# SlippiBoardRev1.net
KiCad netlist of a schematic drawn in EAGLE
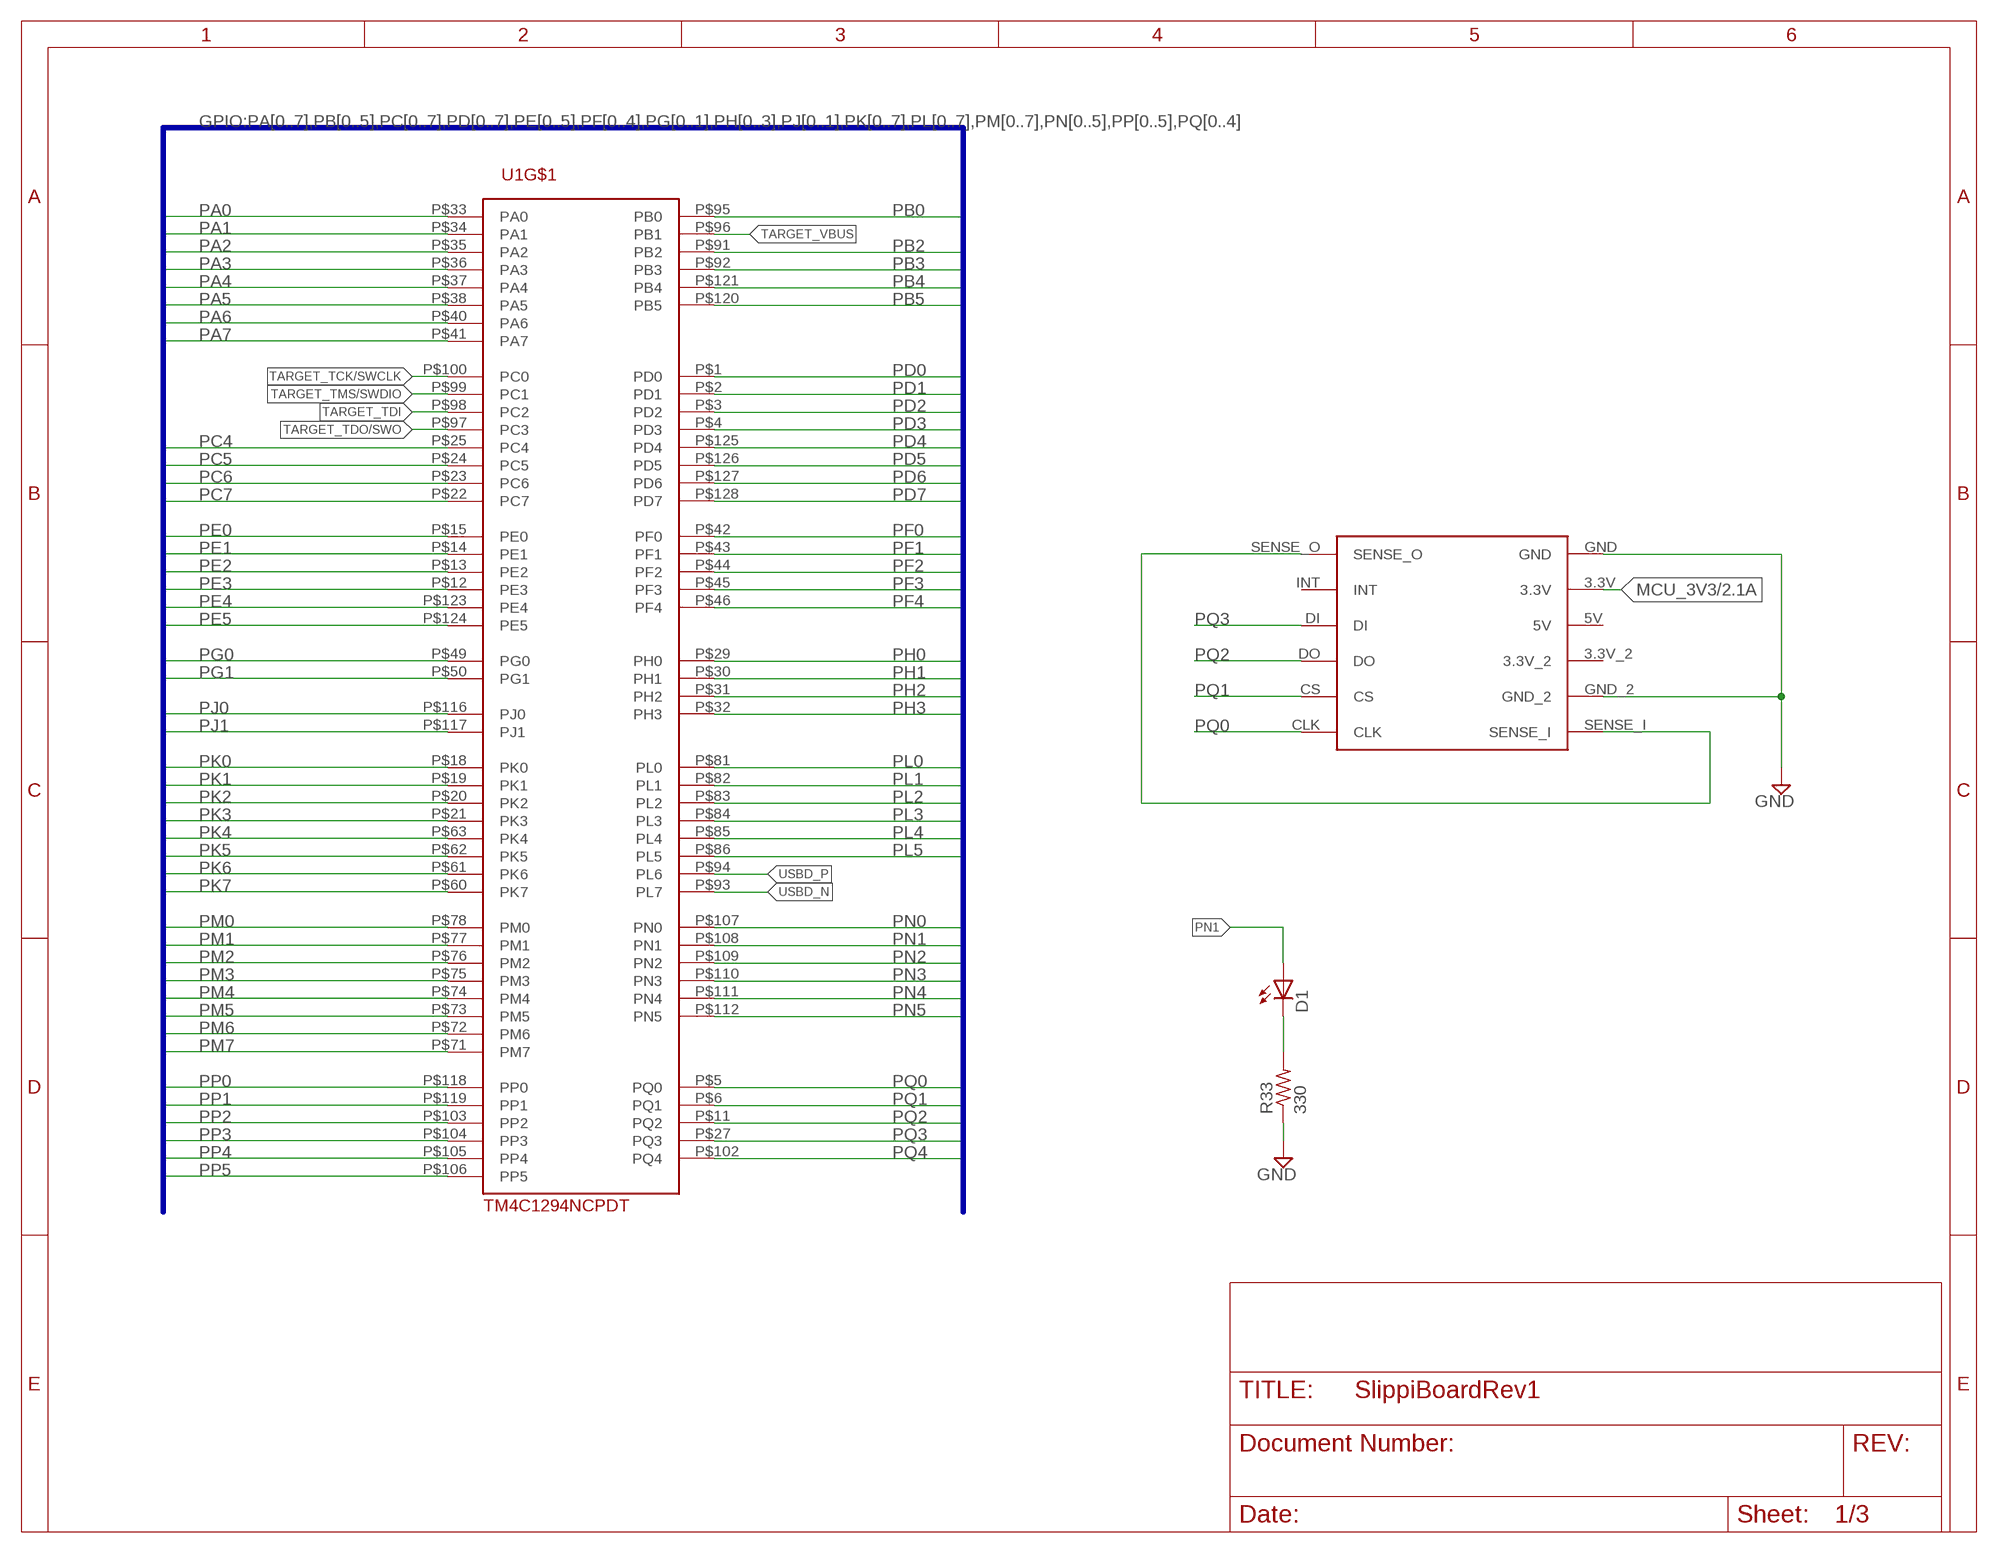
[diagram p0: schematic, sheet 1]
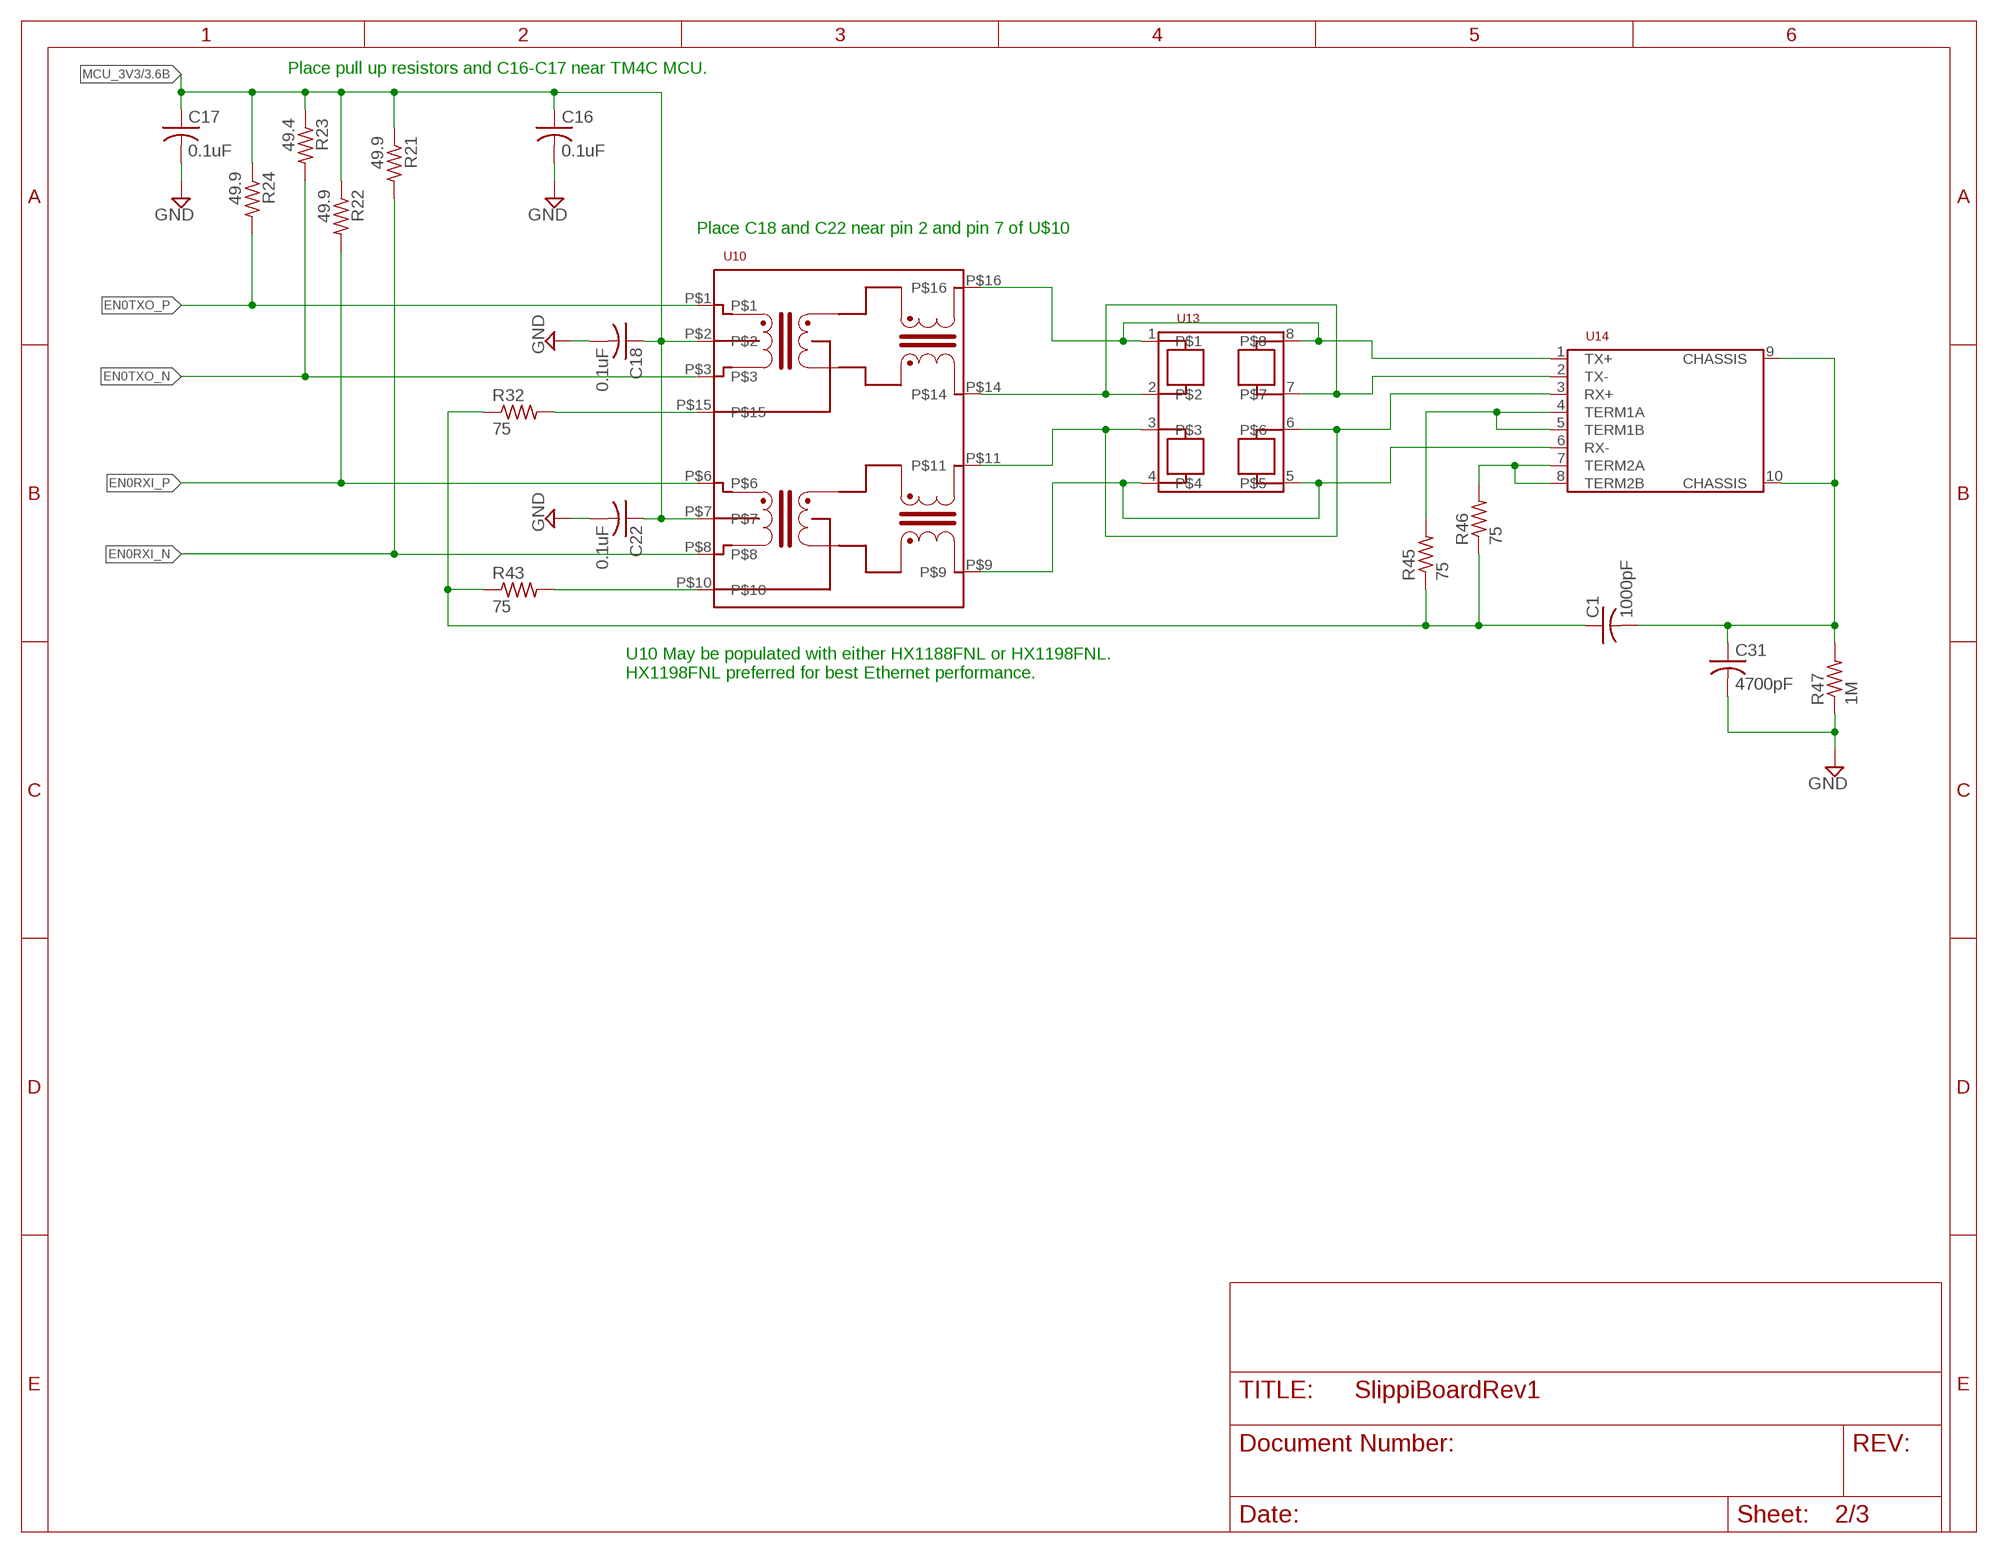
[diagram p1: schematic, sheet 2]
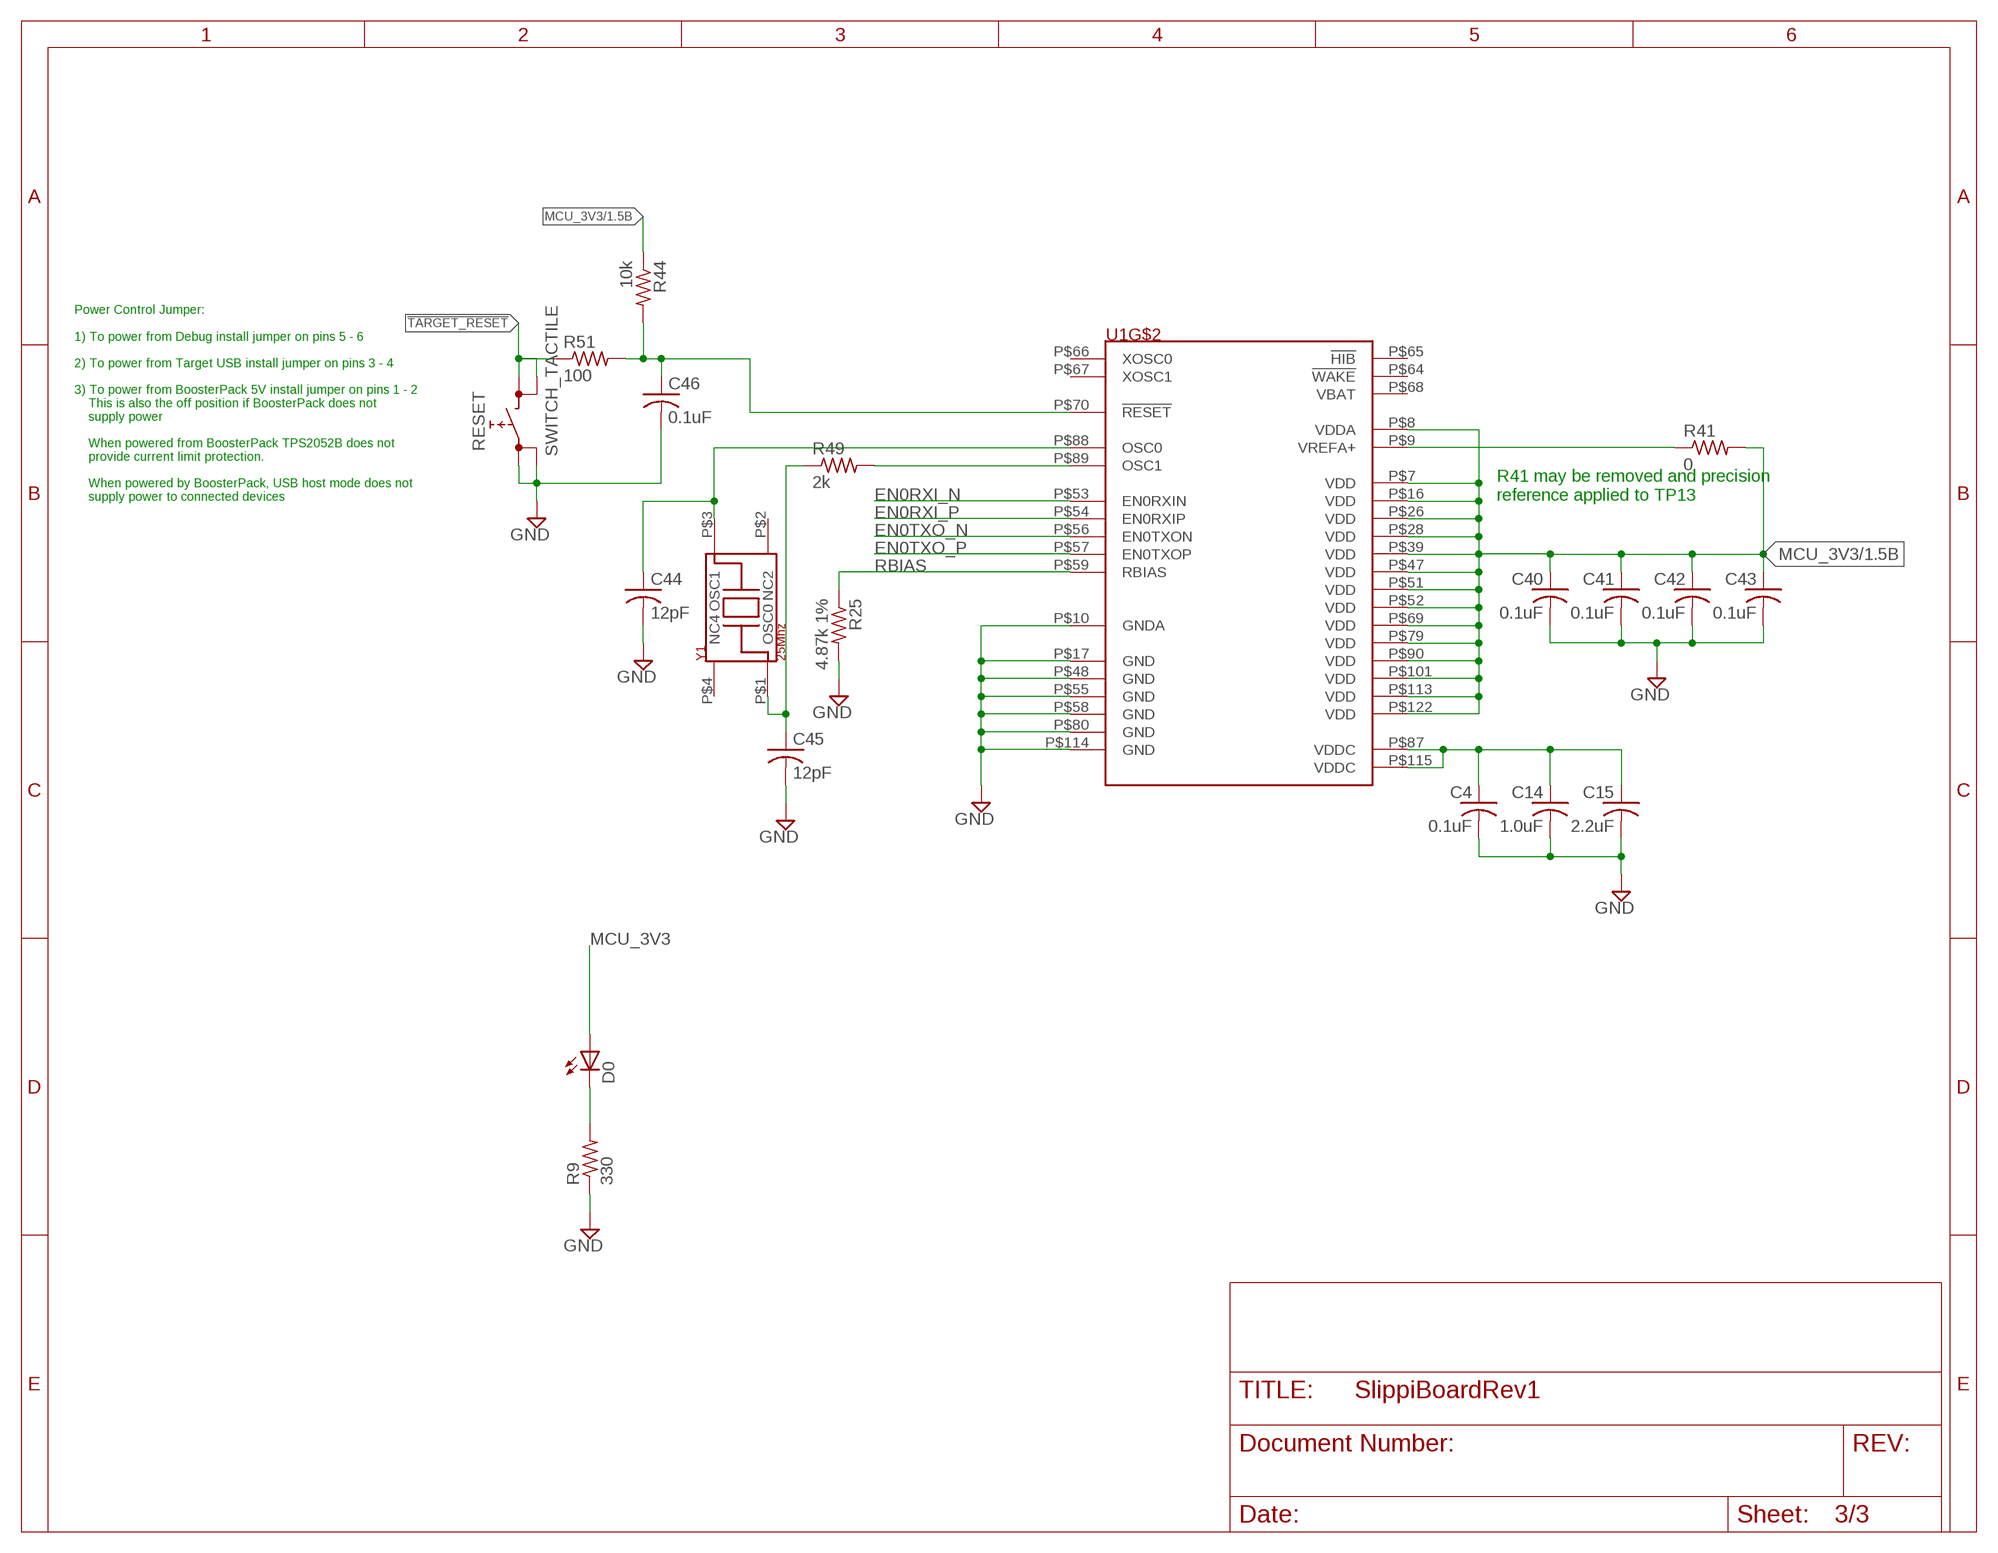
[diagram p2: schematic, sheet 3]

(export (version "E")
  (design (tool "Eeschema 10.0.6"))
  (components
    (comp (ref "D1")
      (value "LEDCHIPLED_0603")
      (footprint "eagle-import:CHIPLED_0603")
      (libsource (lib "eagle-import") (part "LEDCHIPLED_0603"))
    )
    (comp (ref "R33")
      (value "330")
      (footprint "eagle-import:R0402")
      (libsource (lib "eagle-import") (part "ek-tm4c129exl_R-US_R0402"))
    )
    (comp (ref "U$1")
      (value "GC_MEMCARD_CON")
      (footprint "eagle-import:GC_MEMCARD_CON")
      (libsource (lib "eagle-import") (part "GC_MEMCARD_CON"))
    )
    (comp (ref "U1")
      (value "TM4C1294NCPDT")
      (footprint "eagle-import:TQFP-128")
      (fields (field (name "GNUM") "G50-QF128-C1294-ALH"))
      (libsource (lib "eagle-import") (part "TM4C1294NCPDT"))
    )
    (comp (ref "C4")
      (value "0.1uF")
      (footprint "eagle-import:C0402")
      (libsource (lib "eagle-import") (part "ek-tm4c129exl_C-USC0402"))
    )
    (comp (ref "C14")
      (value "1.0uF")
      (footprint "eagle-import:C0402")
      (libsource (lib "eagle-import") (part "ek-tm4c129exl_C-USC0402"))
    )
    (comp (ref "C15")
      (value "2.2uF")
      (footprint "eagle-import:C0603K")
      (fields (field (name "DIGIKEY_PARTNUM") "311-1451-2-ND"))
      (libsource (lib "eagle-import") (part "ek-tm4c129exl_C-USC0603K"))
    )
    (comp (ref "C40")
      (value "0.1uF")
      (footprint "eagle-import:C0402")
      (libsource (lib "eagle-import") (part "ek-tm4c129exl_C-USC0402"))
    )
    (comp (ref "C41")
      (value "0.1uF")
      (footprint "eagle-import:C0402")
      (libsource (lib "eagle-import") (part "ek-tm4c129exl_C-USC0402"))
    )
    (comp (ref "C42")
      (value "0.1uF")
      (footprint "eagle-import:C0402")
      (libsource (lib "eagle-import") (part "ek-tm4c129exl_C-USC0402"))
    )
    (comp (ref "C43")
      (value "0.1uF")
      (footprint "eagle-import:C0402")
      (libsource (lib "eagle-import") (part "ek-tm4c129exl_C-USC0402"))
    )
    (comp (ref "C44")
      (value "12pF")
      (footprint "eagle-import:C0402")
      (libsource (lib "eagle-import") (part "ek-tm4c129exl_C-USC0402"))
    )
    (comp (ref "C45")
      (value "12pF")
      (footprint "eagle-import:C0402")
      (libsource (lib "eagle-import") (part "ek-tm4c129exl_C-USC0402"))
    )
    (comp (ref "C46")
      (value "0.1uF")
      (footprint "eagle-import:C0402")
      (libsource (lib "eagle-import") (part "ek-tm4c129exl_C-USC0402"))
    )
    (comp (ref "D0")
      (value "LEDCHIPLED_0603")
      (footprint "eagle-import:CHIPLED_0603")
      (libsource (lib "eagle-import") (part "LEDCHIPLED_0603"))
    )
    (comp (ref "R9")
      (value "330")
      (footprint "eagle-import:R0402")
      (libsource (lib "eagle-import") (part "ek-tm4c129exl_R-US_R0402"))
    )
    (comp (ref "R25")
      (value "4.87k 1%")
      (footprint "eagle-import:R0402")
      (libsource (lib "eagle-import") (part "ek-tm4c129exl_R-US_R0402"))
    )
    (comp (ref "R41")
      (value "0")
      (footprint "eagle-import:R0402")
      (libsource (lib "eagle-import") (part "ek-tm4c129exl_R-US_R0402"))
    )
    (comp (ref "R44")
      (value "10k")
      (footprint "eagle-import:R0402")
      (libsource (lib "eagle-import") (part "ek-tm4c129exl_R-US_R0402"))
    )
    (comp (ref "R49")
      (value "2k")
      (footprint "eagle-import:R0402")
      (libsource (lib "eagle-import") (part "ek-tm4c129exl_R-US_R0402"))
    )
    (comp (ref "R51")
      (value "100")
      (footprint "eagle-import:R0402")
      (libsource (lib "eagle-import") (part "ek-tm4c129exl_R-US_R0402"))
    )
    (comp (ref "RESET")
      (value "SWITCH_TACTILE")
      (footprint "eagle-import:SWITCH_6MM_6MM_TE_CON_SMD")
      (libsource (lib "eagle-import") (part "SWITCH_TACTILE"))
    )
    (comp (ref "Y1")
      (value "25Mhz")
      (footprint "eagle-import:NDK3.2X2.5")
      (libsource (lib "eagle-import") (part "NX3225GA"))
    )
    (comp (ref "C1")
      (value "1000pF")
      (footprint "eagle-import:C1210")
      (libsource (lib "eagle-import") (part "C-USC1210"))
    )
    (comp (ref "C16")
      (value "0.1uF")
      (footprint "eagle-import:C0402")
      (libsource (lib "eagle-import") (part "ek-tm4c129exl_C-USC0402"))
    )
    (comp (ref "C17")
      (value "0.1uF")
      (footprint "eagle-import:C0402")
      (libsource (lib "eagle-import") (part "ek-tm4c129exl_C-USC0402"))
    )
    (comp (ref "C18")
      (value "0.1uF")
      (footprint "eagle-import:C0402")
      (libsource (lib "eagle-import") (part "ek-tm4c129exl_C-USC0402"))
    )
    (comp (ref "C22")
      (value "0.1uF")
      (footprint "eagle-import:C0402")
      (libsource (lib "eagle-import") (part "ek-tm4c129exl_C-USC0402"))
    )
    (comp (ref "C31")
      (value "4700pF")
      (footprint "eagle-import:C1812")
      (libsource (lib "eagle-import") (part "ek-tm4c129exl_C-USC1812"))
    )
    (comp (ref "R21")
      (value "49.9")
      (footprint "eagle-import:R0402")
      (libsource (lib "eagle-import") (part "ek-tm4c129exl_R-US_R0402"))
    )
    (comp (ref "R22")
      (value "49.9")
      (footprint "eagle-import:R0402")
      (libsource (lib "eagle-import") (part "ek-tm4c129exl_R-US_R0402"))
    )
    (comp (ref "R23")
      (value "49.4")
      (footprint "eagle-import:R0402")
      (libsource (lib "eagle-import") (part "ek-tm4c129exl_R-US_R0402"))
    )
    (comp (ref "R24")
      (value "49.9")
      (footprint "eagle-import:R0402")
      (libsource (lib "eagle-import") (part "ek-tm4c129exl_R-US_R0402"))
    )
    (comp (ref "R32")
      (value "75")
      (footprint "eagle-import:R0402")
      (libsource (lib "eagle-import") (part "ek-tm4c129exl_R-US_R0402"))
    )
    (comp (ref "R43")
      (value "75")
      (footprint "eagle-import:R0402")
      (libsource (lib "eagle-import") (part "ek-tm4c129exl_R-US_R0402"))
    )
    (comp (ref "R45")
      (value "75")
      (footprint "eagle-import:R0402")
      (libsource (lib "eagle-import") (part "ek-tm4c129exl_R-US_R0402"))
    )
    (comp (ref "R46")
      (value "75")
      (footprint "eagle-import:R0402")
      (libsource (lib "eagle-import") (part "ek-tm4c129exl_R-US_R0402"))
    )
    (comp (ref "R47")
      (value "1M")
      (footprint "eagle-import:R1206")
      (libsource (lib "eagle-import") (part "R-US_R1206"))
    )
    (comp (ref "U10")
      (value "MAG_PULSE_HX1188FNL")
      (footprint "eagle-import:MAG_PULSE_HX1188FNL")
      (libsource (lib "eagle-import") (part "MAG_PULSE_HX1188FNL"))
    )
    (comp (ref "U13")
      (value "SLVU2.8-4")
      (footprint "eagle-import:D8")
      (libsource (lib "eagle-import") (part "SLVU2.8-4"))
    )
    (comp (ref "U14")
      (value "JACK_RJ45_NOMAG_NOLED_TECON")
      (footprint "eagle-import:RJ45_TE_CON_NOMAG_NOLED")
      (libsource (lib "eagle-import") (part "JACK_RJ45_NOMAG_NOLED_TECON"))
    )
  )
  (nets
    (net (code "2") (name "EN0RXI_N") (class "Default")
      (node (ref "R21") (pin "2") (pinfunction "2_2") (pintype "passive"))
      (node (ref "U1") (pin "P$53") (pinfunction "EN0RXIN_P$53") (pintype "bidirectional"))
      (node (ref "U10") (pin "P$8") (pinfunction "P$8_P$8") (pintype "bidirectional"))
    )
    (net (code "3") (name "EN0RXI_P") (class "Default")
      (node (ref "R22") (pin "2") (pinfunction "2_2") (pintype "passive"))
      (node (ref "U1") (pin "P$54") (pinfunction "EN0RXIP_P$54") (pintype "bidirectional"))
      (node (ref "U10") (pin "P$6") (pinfunction "P$6_P$6") (pintype "bidirectional"))
    )
    (net (code "4") (name "EN0TXO_N") (class "Default")
      (node (ref "R23") (pin "2") (pinfunction "2_2") (pintype "passive"))
      (node (ref "U1") (pin "P$56") (pinfunction "EN0TXON_P$56") (pintype "bidirectional"))
      (node (ref "U10") (pin "P$3") (pinfunction "P$3_P$3") (pintype "bidirectional"))
    )
    (net (code "5") (name "EN0TXO_P") (class "Default")
      (node (ref "R24") (pin "2") (pinfunction "2_2") (pintype "passive"))
      (node (ref "U1") (pin "P$57") (pinfunction "EN0TXOP_P$57") (pintype "bidirectional"))
      (node (ref "U10") (pin "P$1") (pinfunction "P$1_P$1") (pintype "bidirectional"))
    )
    (net (code "6") (name "GND") (class "Default")
      (node (ref "C14") (pin "2") (pinfunction "2_2") (pintype "passive"))
      (node (ref "C15") (pin "2") (pinfunction "2_2") (pintype "passive"))
      (node (ref "C16") (pin "2") (pinfunction "2_2") (pintype "passive"))
      (node (ref "C17") (pin "2") (pinfunction "2_2") (pintype "passive"))
      (node (ref "C18") (pin "2") (pinfunction "2_2") (pintype "passive"))
      (node (ref "C22") (pin "2") (pinfunction "2_2") (pintype "passive"))
      (node (ref "C31") (pin "2") (pinfunction "2_2") (pintype "passive"))
      (node (ref "C4") (pin "2") (pinfunction "2_2") (pintype "passive"))
      (node (ref "C40") (pin "2") (pinfunction "2_2") (pintype "passive"))
      (node (ref "C41") (pin "2") (pinfunction "2_2") (pintype "passive"))
      (node (ref "C42") (pin "2") (pinfunction "2_2") (pintype "passive"))
      (node (ref "C43") (pin "2") (pinfunction "2_2") (pintype "passive"))
      (node (ref "C44") (pin "2") (pinfunction "2_2") (pintype "passive"))
      (node (ref "C45") (pin "2") (pinfunction "2_2") (pintype "passive"))
      (node (ref "C46") (pin "2") (pinfunction "2_2") (pintype "passive"))
      (node (ref "R25") (pin "2") (pinfunction "2_2") (pintype "passive"))
      (node (ref "R33") (pin "1") (pinfunction "1_1") (pintype "passive"))
      (node (ref "R47") (pin "1") (pinfunction "1_1") (pintype "passive"))
      (node (ref "R9") (pin "1") (pinfunction "1_1") (pintype "passive"))
      (node (ref "RESET") (pin "P$1") (pinfunction "0_P$1") (pintype "passive"))
      (node (ref "RESET") (pin "P$2") (pinfunction "0_P$2") (pintype "passive"))
      (node (ref "U$1") (pin "GND") (pinfunction "GND_GND") (pintype "bidirectional"))
      (node (ref "U$1") (pin "GND_2") (pinfunction "GND_2_GND_2") (pintype "bidirectional"))
      (node (ref "U1") (pin "P$10") (pinfunction "GNDA_P$10") (pintype "bidirectional"))
      (node (ref "U1") (pin "P$114") (pinfunction "GND_P$114") (pintype "bidirectional"))
      (node (ref "U1") (pin "P$17") (pinfunction "GND_P$17") (pintype "bidirectional"))
      (node (ref "U1") (pin "P$48") (pinfunction "GND_P$48") (pintype "bidirectional"))
      (node (ref "U1") (pin "P$55") (pinfunction "GND_P$55") (pintype "bidirectional"))
      (node (ref "U1") (pin "P$58") (pinfunction "GND_P$58") (pintype "bidirectional"))
      (node (ref "U1") (pin "P$80") (pinfunction "GND_P$80") (pintype "bidirectional"))
    )
    (net (code "7") (name "MCU_3V3") (class "Default")
      (node (ref "C16") (pin "1") (pinfunction "1_1") (pintype "passive"))
      (node (ref "C17") (pin "1") (pinfunction "1_1") (pintype "passive"))
      (node (ref "C18") (pin "1") (pinfunction "1_1") (pintype "passive"))
      (node (ref "C22") (pin "1") (pinfunction "1_1") (pintype "passive"))
      (node (ref "C40") (pin "1") (pinfunction "1_1") (pintype "passive"))
      (node (ref "C41") (pin "1") (pinfunction "1_1") (pintype "passive"))
      (node (ref "C42") (pin "1") (pinfunction "1_1") (pintype "passive"))
      (node (ref "C43") (pin "1") (pinfunction "1_1") (pintype "passive"))
      (node (ref "D0") (pin "A") (pinfunction "A_A") (pintype "passive"))
      (node (ref "R21") (pin "1") (pinfunction "1_1") (pintype "passive"))
      (node (ref "R22") (pin "1") (pinfunction "1_1") (pintype "passive"))
      (node (ref "R23") (pin "1") (pinfunction "1_1") (pintype "passive"))
      (node (ref "R24") (pin "1") (pinfunction "1_1") (pintype "passive"))
      (node (ref "R41") (pin "2") (pinfunction "2_2") (pintype "passive"))
      (node (ref "R44") (pin "1") (pinfunction "1_1") (pintype "passive"))
      (node (ref "U$1") (pin "3.3V") (pinfunction "3.3V_3.3V") (pintype "bidirectional"))
      (node (ref "U1") (pin "P$101") (pinfunction "VDD_P$101") (pintype "bidirectional"))
      (node (ref "U1") (pin "P$113") (pinfunction "VDD_P$113") (pintype "bidirectional"))
      (node (ref "U1") (pin "P$122") (pinfunction "VDD_P$122") (pintype "bidirectional"))
      (node (ref "U1") (pin "P$16") (pinfunction "VDD_P$16") (pintype "bidirectional"))
      (node (ref "U1") (pin "P$26") (pinfunction "VDD_P$26") (pintype "bidirectional"))
      (node (ref "U1") (pin "P$28") (pinfunction "VDD_P$28") (pintype "bidirectional"))
      (node (ref "U1") (pin "P$39") (pinfunction "VDD_P$39") (pintype "bidirectional"))
      (node (ref "U1") (pin "P$47") (pinfunction "VDD_P$47") (pintype "bidirectional"))
      (node (ref "U1") (pin "P$51") (pinfunction "VDD_P$51") (pintype "bidirectional"))
      (node (ref "U1") (pin "P$52") (pinfunction "VDD_P$52") (pintype "bidirectional"))
      (node (ref "U1") (pin "P$69") (pinfunction "VDD_P$69") (pintype "bidirectional"))
      (node (ref "U1") (pin "P$7") (pinfunction "VDD_P$7") (pintype "bidirectional"))
      (node (ref "U1") (pin "P$79") (pinfunction "VDD_P$79") (pintype "bidirectional"))
      (node (ref "U1") (pin "P$8") (pinfunction "VDDA_P$8") (pintype "bidirectional"))
      (node (ref "U1") (pin "P$90") (pinfunction "VDD_P$90") (pintype "bidirectional"))
      (node (ref "U10") (pin "P$2") (pinfunction "P$2_P$2") (pintype "bidirectional"))
      (node (ref "U10") (pin "P$7") (pinfunction "P$7_P$7") (pintype "bidirectional"))
    )
    (net (code "8") (name "Net-(C1-Pad1)") (class "Default")
      (node (ref "C1") (pin "1") (pinfunction "1_1") (pintype "passive"))
      (node (ref "R32") (pin "1") (pinfunction "1_1") (pintype "passive"))
      (node (ref "R43") (pin "1") (pinfunction "1_1") (pintype "passive"))
      (node (ref "R45") (pin "1") (pinfunction "1_1") (pintype "passive"))
      (node (ref "R46") (pin "1") (pinfunction "1_1") (pintype "passive"))
    )
    (net (code "9") (name "Net-(C1-Pad2)") (class "Default")
      (node (ref "C1") (pin "2") (pinfunction "2_2") (pintype "passive"))
      (node (ref "C31") (pin "1") (pinfunction "1_1") (pintype "passive"))
      (node (ref "R47") (pin "2") (pinfunction "2_2") (pintype "passive"))
      (node (ref "U14") (pin "10") (pinfunction "CHASSIS_10") (pintype "bidirectional"))
      (node (ref "U14") (pin "9") (pinfunction "CHASSIS_9") (pintype "bidirectional"))
    )
    (net (code "10") (name "Net-(C14-Pad1)") (class "Default")
      (node (ref "C14") (pin "1") (pinfunction "1_1") (pintype "passive"))
      (node (ref "C15") (pin "1") (pinfunction "1_1") (pintype "passive"))
      (node (ref "C4") (pin "1") (pinfunction "1_1") (pintype "passive"))
      (node (ref "U1") (pin "P$115") (pinfunction "VDDC_P$115") (pintype "bidirectional"))
      (node (ref "U1") (pin "P$87") (pinfunction "VDDC_P$87") (pintype "bidirectional"))
    )
    (net (code "11") (name "Net-(D0-PadC)") (class "Default")
      (node (ref "D0") (pin "C") (pinfunction "C_C") (pintype "passive"))
      (node (ref "R9") (pin "2") (pinfunction "2_2") (pintype "passive"))
    )
    (net (code "12") (name "Net-(D1-PadC)") (class "Default")
      (node (ref "D1") (pin "C") (pinfunction "C_C") (pintype "passive"))
      (node (ref "R33") (pin "2") (pinfunction "2_2") (pintype "passive"))
    )
    (net (code "13") (name "Net-(R32-Pad2)") (class "Default")
      (node (ref "R32") (pin "2") (pinfunction "2_2") (pintype "passive"))
      (node (ref "U10") (pin "P$15") (pinfunction "P$15_P$15") (pintype "bidirectional"))
    )
    (net (code "14") (name "Net-(R43-Pad2)") (class "Default")
      (node (ref "R43") (pin "2") (pinfunction "2_2") (pintype "passive"))
      (node (ref "U10") (pin "P$10") (pinfunction "P$10_P$10") (pintype "bidirectional"))
    )
    (net (code "15") (name "Net-(U$1-PadSENSE_I)") (class "Default")
      (node (ref "U$1") (pin "SENSE_I") (pinfunction "SENSE_I_SENSE_I") (pintype "bidirectional"))
      (node (ref "U$1") (pin "SENSE_O") (pinfunction "SENSE_O_SENSE_O") (pintype "bidirectional"))
    )
    (net (code "16") (name "Net-(U1B-OSC0)") (class "Default")
      (node (ref "C44") (pin "1") (pinfunction "1_1") (pintype "passive"))
      (node (ref "U1") (pin "P$88") (pinfunction "OSC0_P$88") (pintype "bidirectional"))
      (node (ref "Y1") (pin "P$3") (pinfunction "OSC1_P$3") (pintype "bidirectional"))
    )
    (net (code "17") (name "Net-(U1B-OSC1)") (class "Default")
      (node (ref "R49") (pin "2") (pinfunction "2_2") (pintype "passive"))
      (node (ref "U1") (pin "P$89") (pinfunction "OSC1_P$89") (pintype "bidirectional"))
    )
    (net (code "18") (name "Net-(U1B-VREFA+)") (class "Default")
      (node (ref "R41") (pin "1") (pinfunction "1_1") (pintype "passive"))
      (node (ref "U1") (pin "P$9") (pinfunction "VREFA+_P$9") (pintype "bidirectional"))
    )
    (net (code "19") (name "Net-(U1B-~{RESET})") (class "Default")
      (node (ref "C46") (pin "1") (pinfunction "1_1") (pintype "passive"))
      (node (ref "R44") (pin "2") (pinfunction "2_2") (pintype "passive"))
      (node (ref "R51") (pin "2") (pinfunction "2_2") (pintype "passive"))
      (node (ref "U1") (pin "P$70") (pinfunction "~{RESET}_P$70") (pintype "bidirectional"))
    )
    (net (code "20") (name "Net-(U13-P$1)") (class "Default")
      (node (ref "U10") (pin "P$16") (pinfunction "P$16_P$16") (pintype "bidirectional"))
      (node (ref "U13") (pin "1") (pinfunction "P$1_1") (pintype "bidirectional"))
      (node (ref "U13") (pin "8") (pinfunction "P$8_8") (pintype "bidirectional"))
      (node (ref "U14") (pin "1") (pinfunction "TX+_1") (pintype "bidirectional"))
    )
    (net (code "21") (name "Net-(U13-P$2)") (class "Default")
      (node (ref "U10") (pin "P$14") (pinfunction "P$14_P$14") (pintype "bidirectional"))
      (node (ref "U13") (pin "2") (pinfunction "P$2_2") (pintype "bidirectional"))
      (node (ref "U13") (pin "7") (pinfunction "P$7_7") (pintype "bidirectional"))
      (node (ref "U14") (pin "2") (pinfunction "TX-_2") (pintype "bidirectional"))
    )
    (net (code "22") (name "Net-(U13-P$3)") (class "Default")
      (node (ref "U10") (pin "P$11") (pinfunction "P$11_P$11") (pintype "bidirectional"))
      (node (ref "U13") (pin "3") (pinfunction "P$3_3") (pintype "bidirectional"))
      (node (ref "U13") (pin "6") (pinfunction "P$6_6") (pintype "bidirectional"))
      (node (ref "U14") (pin "3") (pinfunction "RX+_3") (pintype "bidirectional"))
    )
    (net (code "23") (name "Net-(U13-P$4)") (class "Default")
      (node (ref "U10") (pin "P$9") (pinfunction "P$9_P$9") (pintype "bidirectional"))
      (node (ref "U13") (pin "4") (pinfunction "P$4_4") (pintype "bidirectional"))
      (node (ref "U13") (pin "5") (pinfunction "P$5_5") (pintype "bidirectional"))
      (node (ref "U14") (pin "6") (pinfunction "RX-_6") (pintype "bidirectional"))
    )
    (net (code "24") (name "Net-(U14-TERM1A)") (class "Default")
      (node (ref "R45") (pin "2") (pinfunction "2_2") (pintype "passive"))
      (node (ref "U14") (pin "4") (pinfunction "TERM1A_4") (pintype "bidirectional"))
      (node (ref "U14") (pin "5") (pinfunction "TERM1B_5") (pintype "bidirectional"))
    )
    (net (code "25") (name "Net-(U14-TERM2A)") (class "Default")
      (node (ref "R46") (pin "2") (pinfunction "2_2") (pintype "passive"))
      (node (ref "U14") (pin "7") (pinfunction "TERM2A_7") (pintype "bidirectional"))
      (node (ref "U14") (pin "8") (pinfunction "TERM2B_8") (pintype "bidirectional"))
    )
    (net (code "26") (name "Net-(Y1-OSC0)") (class "Default")
      (node (ref "C45") (pin "1") (pinfunction "1_1") (pintype "passive"))
      (node (ref "R49") (pin "1") (pinfunction "1_1") (pintype "passive"))
      (node (ref "Y1") (pin "P$1") (pinfunction "OSC0_P$1") (pintype "bidirectional"))
    )
    (net (code "27") (name "PA0") (class "Default")
      (node (ref "U1") (pin "P$33") (pinfunction "PA0_P$33") (pintype "bidirectional"))
    )
    (net (code "28") (name "PA1") (class "Default")
      (node (ref "U1") (pin "P$34") (pinfunction "PA1_P$34") (pintype "bidirectional"))
    )
    (net (code "29") (name "PA2") (class "Default")
      (node (ref "U1") (pin "P$35") (pinfunction "PA2_P$35") (pintype "bidirectional"))
    )
    (net (code "30") (name "PA3") (class "Default")
      (node (ref "U1") (pin "P$36") (pinfunction "PA3_P$36") (pintype "bidirectional"))
    )
    (net (code "31") (name "PA4") (class "Default")
      (node (ref "U1") (pin "P$37") (pinfunction "PA4_P$37") (pintype "bidirectional"))
    )
    (net (code "32") (name "PA5") (class "Default")
      (node (ref "U1") (pin "P$38") (pinfunction "PA5_P$38") (pintype "bidirectional"))
    )
    (net (code "33") (name "PA6") (class "Default")
      (node (ref "U1") (pin "P$40") (pinfunction "PA6_P$40") (pintype "bidirectional"))
    )
    (net (code "34") (name "PA7") (class "Default")
      (node (ref "U1") (pin "P$41") (pinfunction "PA7_P$41") (pintype "bidirectional"))
    )
    (net (code "35") (name "PB0") (class "Default")
      (node (ref "U1") (pin "P$95") (pinfunction "PB0_P$95") (pintype "bidirectional"))
    )
    (net (code "36") (name "PB2") (class "Default")
      (node (ref "U1") (pin "P$91") (pinfunction "PB2_P$91") (pintype "bidirectional"))
    )
    (net (code "37") (name "PB3") (class "Default")
      (node (ref "U1") (pin "P$92") (pinfunction "PB3_P$92") (pintype "bidirectional"))
    )
    (net (code "38") (name "PB4") (class "Default")
      (node (ref "U1") (pin "P$121") (pinfunction "PB4_P$121") (pintype "bidirectional"))
    )
    (net (code "39") (name "PB5") (class "Default")
      (node (ref "U1") (pin "P$120") (pinfunction "PB5_P$120") (pintype "bidirectional"))
    )
    (net (code "40") (name "PC4") (class "Default")
      (node (ref "U1") (pin "P$25") (pinfunction "PC4_P$25") (pintype "bidirectional"))
    )
    (net (code "41") (name "PC5") (class "Default")
      (node (ref "U1") (pin "P$24") (pinfunction "PC5_P$24") (pintype "bidirectional"))
    )
    (net (code "42") (name "PC6") (class "Default")
      (node (ref "U1") (pin "P$23") (pinfunction "PC6_P$23") (pintype "bidirectional"))
    )
    (net (code "43") (name "PC7") (class "Default")
      (node (ref "U1") (pin "P$22") (pinfunction "PC7_P$22") (pintype "bidirectional"))
    )
    (net (code "44") (name "PD0") (class "Default")
      (node (ref "U1") (pin "P$1") (pinfunction "PD0_P$1") (pintype "bidirectional"))
    )
    (net (code "45") (name "PD1") (class "Default")
      (node (ref "U1") (pin "P$2") (pinfunction "PD1_P$2") (pintype "bidirectional"))
    )
    (net (code "46") (name "PD2") (class "Default")
      (node (ref "U1") (pin "P$3") (pinfunction "PD2_P$3") (pintype "bidirectional"))
    )
    (net (code "47") (name "PD3") (class "Default")
      (node (ref "U1") (pin "P$4") (pinfunction "PD3_P$4") (pintype "bidirectional"))
    )
    (net (code "48") (name "PD4") (class "Default")
      (node (ref "U1") (pin "P$125") (pinfunction "PD4_P$125") (pintype "bidirectional"))
    )
    (net (code "49") (name "PD5") (class "Default")
      (node (ref "U1") (pin "P$126") (pinfunction "PD5_P$126") (pintype "bidirectional"))
    )
    (net (code "50") (name "PD6") (class "Default")
      (node (ref "U1") (pin "P$127") (pinfunction "PD6_P$127") (pintype "bidirectional"))
    )
    (net (code "51") (name "PD7") (class "Default")
      (node (ref "U1") (pin "P$128") (pinfunction "PD7_P$128") (pintype "bidirectional"))
    )
    (net (code "52") (name "PE0") (class "Default")
      (node (ref "U1") (pin "P$15") (pinfunction "PE0_P$15") (pintype "bidirectional"))
    )
    (net (code "53") (name "PE1") (class "Default")
      (node (ref "U1") (pin "P$14") (pinfunction "PE1_P$14") (pintype "bidirectional"))
    )
    (net (code "54") (name "PE2") (class "Default")
      (node (ref "U1") (pin "P$13") (pinfunction "PE2_P$13") (pintype "bidirectional"))
    )
    (net (code "55") (name "PE3") (class "Default")
      (node (ref "U1") (pin "P$12") (pinfunction "PE3_P$12") (pintype "bidirectional"))
    )
    (net (code "56") (name "PE4") (class "Default")
      (node (ref "U1") (pin "P$123") (pinfunction "PE4_P$123") (pintype "bidirectional"))
    )
    (net (code "57") (name "PE5") (class "Default")
      (node (ref "U1") (pin "P$124") (pinfunction "PE5_P$124") (pintype "bidirectional"))
    )
    (net (code "58") (name "PF0") (class "Default")
      (node (ref "U1") (pin "P$42") (pinfunction "PF0_P$42") (pintype "bidirectional"))
    )
    (net (code "59") (name "PF1") (class "Default")
      (node (ref "U1") (pin "P$43") (pinfunction "PF1_P$43") (pintype "bidirectional"))
    )
    (net (code "60") (name "PF2") (class "Default")
      (node (ref "U1") (pin "P$44") (pinfunction "PF2_P$44") (pintype "bidirectional"))
    )
    (net (code "61") (name "PF3") (class "Default")
      (node (ref "U1") (pin "P$45") (pinfunction "PF3_P$45") (pintype "bidirectional"))
    )
    (net (code "62") (name "PF4") (class "Default")
      (node (ref "U1") (pin "P$46") (pinfunction "PF4_P$46") (pintype "bidirectional"))
    )
    (net (code "63") (name "PG0") (class "Default")
      (node (ref "U1") (pin "P$49") (pinfunction "PG0_P$49") (pintype "bidirectional"))
    )
    (net (code "64") (name "PG1") (class "Default")
      (node (ref "U1") (pin "P$50") (pinfunction "PG1_P$50") (pintype "bidirectional"))
    )
    (net (code "65") (name "PH0") (class "Default")
      (node (ref "U1") (pin "P$29") (pinfunction "PH0_P$29") (pintype "bidirectional"))
    )
    (net (code "66") (name "PH1") (class "Default")
      (node (ref "U1") (pin "P$30") (pinfunction "PH1_P$30") (pintype "bidirectional"))
    )
    (net (code "67") (name "PH2") (class "Default")
      (node (ref "U1") (pin "P$31") (pinfunction "PH2_P$31") (pintype "bidirectional"))
    )
    (net (code "68") (name "PH3") (class "Default")
      (node (ref "U1") (pin "P$32") (pinfunction "PH3_P$32") (pintype "bidirectional"))
    )
    (net (code "69") (name "PJ0") (class "Default")
      (node (ref "U1") (pin "P$116") (pinfunction "PJ0_P$116") (pintype "bidirectional"))
    )
    (net (code "70") (name "PJ1") (class "Default")
      (node (ref "U1") (pin "P$117") (pinfunction "PJ1_P$117") (pintype "bidirectional"))
    )
    (net (code "71") (name "PK0") (class "Default")
      (node (ref "U1") (pin "P$18") (pinfunction "PK0_P$18") (pintype "bidirectional"))
    )
    (net (code "72") (name "PK1") (class "Default")
      (node (ref "U1") (pin "P$19") (pinfunction "PK1_P$19") (pintype "bidirectional"))
    )
    (net (code "73") (name "PK2") (class "Default")
      (node (ref "U1") (pin "P$20") (pinfunction "PK2_P$20") (pintype "bidirectional"))
    )
    (net (code "74") (name "PK3") (class "Default")
      (node (ref "U1") (pin "P$21") (pinfunction "PK3_P$21") (pintype "bidirectional"))
    )
    (net (code "75") (name "PK4") (class "Default")
      (node (ref "U1") (pin "P$63") (pinfunction "PK4_P$63") (pintype "bidirectional"))
    )
    (net (code "76") (name "PK5") (class "Default")
      (node (ref "U1") (pin "P$62") (pinfunction "PK5_P$62") (pintype "bidirectional"))
    )
    (net (code "77") (name "PK6") (class "Default")
      (node (ref "U1") (pin "P$61") (pinfunction "PK6_P$61") (pintype "bidirectional"))
    )
    (net (code "78") (name "PK7") (class "Default")
      (node (ref "U1") (pin "P$60") (pinfunction "PK7_P$60") (pintype "bidirectional"))
    )
    (net (code "79") (name "PL0") (class "Default")
      (node (ref "U1") (pin "P$81") (pinfunction "PL0_P$81") (pintype "bidirectional"))
    )
    (net (code "80") (name "PL1") (class "Default")
      (node (ref "U1") (pin "P$82") (pinfunction "PL1_P$82") (pintype "bidirectional"))
    )
    (net (code "81") (name "PL2") (class "Default")
      (node (ref "U1") (pin "P$83") (pinfunction "PL2_P$83") (pintype "bidirectional"))
    )
    (net (code "82") (name "PL3") (class "Default")
      (node (ref "U1") (pin "P$84") (pinfunction "PL3_P$84") (pintype "bidirectional"))
    )
    (net (code "83") (name "PL4") (class "Default")
      (node (ref "U1") (pin "P$85") (pinfunction "PL4_P$85") (pintype "bidirectional"))
    )
    (net (code "84") (name "PL5") (class "Default")
      (node (ref "U1") (pin "P$86") (pinfunction "PL5_P$86") (pintype "bidirectional"))
    )
    (net (code "85") (name "PM0") (class "Default")
      (node (ref "U1") (pin "P$78") (pinfunction "PM0_P$78") (pintype "bidirectional"))
    )
    (net (code "86") (name "PM1") (class "Default")
      (node (ref "U1") (pin "P$77") (pinfunction "PM1_P$77") (pintype "bidirectional"))
    )
    (net (code "87") (name "PM2") (class "Default")
      (node (ref "U1") (pin "P$76") (pinfunction "PM2_P$76") (pintype "bidirectional"))
    )
    (net (code "88") (name "PM3") (class "Default")
      (node (ref "U1") (pin "P$75") (pinfunction "PM3_P$75") (pintype "bidirectional"))
    )
    (net (code "89") (name "PM4") (class "Default")
      (node (ref "U1") (pin "P$74") (pinfunction "PM4_P$74") (pintype "bidirectional"))
    )
    (net (code "90") (name "PM5") (class "Default")
      (node (ref "U1") (pin "P$73") (pinfunction "PM5_P$73") (pintype "bidirectional"))
    )
    (net (code "91") (name "PM6") (class "Default")
      (node (ref "U1") (pin "P$72") (pinfunction "PM6_P$72") (pintype "bidirectional"))
    )
    (net (code "92") (name "PM7") (class "Default")
      (node (ref "U1") (pin "P$71") (pinfunction "PM7_P$71") (pintype "bidirectional"))
    )
    (net (code "93") (name "PN0") (class "Default")
      (node (ref "U1") (pin "P$107") (pinfunction "PN0_P$107") (pintype "bidirectional"))
    )
    (net (code "94") (name "PN1") (class "Default")
      (node (ref "D1") (pin "A") (pinfunction "A_A") (pintype "passive"))
      (node (ref "U1") (pin "P$108") (pinfunction "PN1_P$108") (pintype "bidirectional"))
    )
    (net (code "95") (name "PN2") (class "Default")
      (node (ref "U1") (pin "P$109") (pinfunction "PN2_P$109") (pintype "bidirectional"))
    )
    (net (code "96") (name "PN3") (class "Default")
      (node (ref "U1") (pin "P$110") (pinfunction "PN3_P$110") (pintype "bidirectional"))
    )
    (net (code "97") (name "PN4") (class "Default")
      (node (ref "U1") (pin "P$111") (pinfunction "PN4_P$111") (pintype "bidirectional"))
    )
    (net (code "98") (name "PN5") (class "Default")
      (node (ref "U1") (pin "P$112") (pinfunction "PN5_P$112") (pintype "bidirectional"))
    )
    (net (code "99") (name "PP0") (class "Default")
      (node (ref "U1") (pin "P$118") (pinfunction "PP0_P$118") (pintype "bidirectional"))
    )
    (net (code "100") (name "PP1") (class "Default")
      (node (ref "U1") (pin "P$119") (pinfunction "PP1_P$119") (pintype "bidirectional"))
    )
    (net (code "101") (name "PP2") (class "Default")
      (node (ref "U1") (pin "P$103") (pinfunction "PP2_P$103") (pintype "bidirectional"))
    )
    (net (code "102") (name "PP3") (class "Default")
      (node (ref "U1") (pin "P$104") (pinfunction "PP3_P$104") (pintype "bidirectional"))
    )
    (net (code "103") (name "PP4") (class "Default")
      (node (ref "U1") (pin "P$105") (pinfunction "PP4_P$105") (pintype "bidirectional"))
    )
    (net (code "104") (name "PP5") (class "Default")
      (node (ref "U1") (pin "P$106") (pinfunction "PP5_P$106") (pintype "bidirectional"))
    )
    (net (code "105") (name "PQ0") (class "Default")
      (node (ref "U$1") (pin "CLK") (pinfunction "CLK_CLK") (pintype "bidirectional"))
      (node (ref "U1") (pin "P$5") (pinfunction "PQ0_P$5") (pintype "bidirectional"))
    )
    (net (code "106") (name "PQ1") (class "Default")
      (node (ref "U$1") (pin "CS") (pinfunction "CS_CS") (pintype "bidirectional"))
      (node (ref "U1") (pin "P$6") (pinfunction "PQ1_P$6") (pintype "bidirectional"))
    )
    (net (code "107") (name "PQ2") (class "Default")
      (node (ref "U$1") (pin "DO") (pinfunction "DO_DO") (pintype "bidirectional"))
      (node (ref "U1") (pin "P$11") (pinfunction "PQ2_P$11") (pintype "bidirectional"))
    )
    (net (code "108") (name "PQ3") (class "Default")
      (node (ref "U$1") (pin "DI") (pinfunction "DI_DI") (pintype "bidirectional"))
      (node (ref "U1") (pin "P$27") (pinfunction "PQ3_P$27") (pintype "bidirectional"))
    )
    (net (code "109") (name "PQ4") (class "Default")
      (node (ref "U1") (pin "P$102") (pinfunction "PQ4_P$102") (pintype "bidirectional"))
    )
    (net (code "110") (name "RBIAS") (class "Default")
      (node (ref "R25") (pin "1") (pinfunction "1_1") (pintype "passive"))
      (node (ref "U1") (pin "P$59") (pinfunction "RBIAS_P$59") (pintype "bidirectional"))
    )
    (net (code "111") (name "TARGET_TCK{slash}SWCLK") (class "Default")
      (node (ref "U1") (pin "P$100") (pinfunction "PC0_P$100") (pintype "bidirectional"))
    )
    (net (code "112") (name "TARGET_TDI") (class "Default")
      (node (ref "U1") (pin "P$98") (pinfunction "PC2_P$98") (pintype "bidirectional"))
    )
    (net (code "113") (name "TARGET_TDO{slash}SWO") (class "Default")
      (node (ref "U1") (pin "P$97") (pinfunction "PC3_P$97") (pintype "bidirectional"))
    )
    (net (code "114") (name "TARGET_TMS{slash}SWDIO") (class "Default")
      (node (ref "U1") (pin "P$99") (pinfunction "PC1_P$99") (pintype "bidirectional"))
    )
    (net (code "115") (name "TARGET_VBUS") (class "Default")
      (node (ref "U1") (pin "P$96") (pinfunction "PB1_P$96") (pintype "bidirectional"))
    )
    (net (code "116") (name "USBD_N") (class "Default")
      (node (ref "U1") (pin "P$93") (pinfunction "PL7_P$93") (pintype "bidirectional"))
    )
    (net (code "117") (name "USBD_P") (class "Default")
      (node (ref "U1") (pin "P$94") (pinfunction "PL6_P$94") (pintype "bidirectional"))
    )
    (net (code "118") (name "unconnected-(U$1-Pad3.3V_2)") (class "Default")
      (node (ref "U$1") (pin "3.3V_2") (pinfunction "3.3V_2_3.3V_2") (pintype "bidirectional"))
    )
    (net (code "119") (name "unconnected-(U$1-Pad5V)") (class "Default")
      (node (ref "U$1") (pin "5V") (pinfunction "5V_5V") (pintype "bidirectional"))
    )
    (net (code "120") (name "unconnected-(U$1-PadINT)") (class "Default")
      (node (ref "U$1") (pin "INT") (pinfunction "INT_INT") (pintype "bidirectional"))
    )
    (net (code "121") (name "unconnected-(U1B-VBAT-PadP$68)") (class "Default")
      (node (ref "U1") (pin "P$68") (pinfunction "VBAT_P$68") (pintype "bidirectional"))
    )
    (net (code "122") (name "unconnected-(U1B-XOSC0-PadP$66)") (class "Default")
      (node (ref "U1") (pin "P$66") (pinfunction "XOSC0_P$66") (pintype "bidirectional"))
    )
    (net (code "123") (name "unconnected-(U1B-XOSC1-PadP$67)") (class "Default")
      (node (ref "U1") (pin "P$67") (pinfunction "XOSC1_P$67") (pintype "bidirectional"))
    )
    (net (code "124") (name "unconnected-(U1B-~{HIB}-PadP$65)") (class "Default")
      (node (ref "U1") (pin "P$65") (pinfunction "~{HIB}_P$65") (pintype "bidirectional"))
    )
    (net (code "125") (name "unconnected-(U1B-~{WAKE}-PadP$64)") (class "Default")
      (node (ref "U1") (pin "P$64") (pinfunction "~{WAKE}_P$64") (pintype "bidirectional"))
    )
    (net (code "126") (name "unconnected-(Y1-NC2-PadP$2)") (class "Default")
      (node (ref "Y1") (pin "P$2") (pinfunction "NC2_P$2") (pintype "bidirectional"))
    )
    (net (code "127") (name "unconnected-(Y1-NC4-PadP$4)") (class "Default")
      (node (ref "Y1") (pin "P$4") (pinfunction "NC4_P$4") (pintype "bidirectional"))
    )
    (net (code "128") (name "~{TARGET_RESET}") (class "Default")
      (node (ref "R51") (pin "1") (pinfunction "1_1") (pintype "passive"))
      (node (ref "RESET") (pin "P$3") (pinfunction "1_P$3") (pintype "passive"))
      (node (ref "RESET") (pin "P$4") (pinfunction "1_P$4") (pintype "passive"))
    )
  )
)
